# Amiga_USB_Serial_Adapter.net
KiCad netlist of a schematic drawn in EAGLE
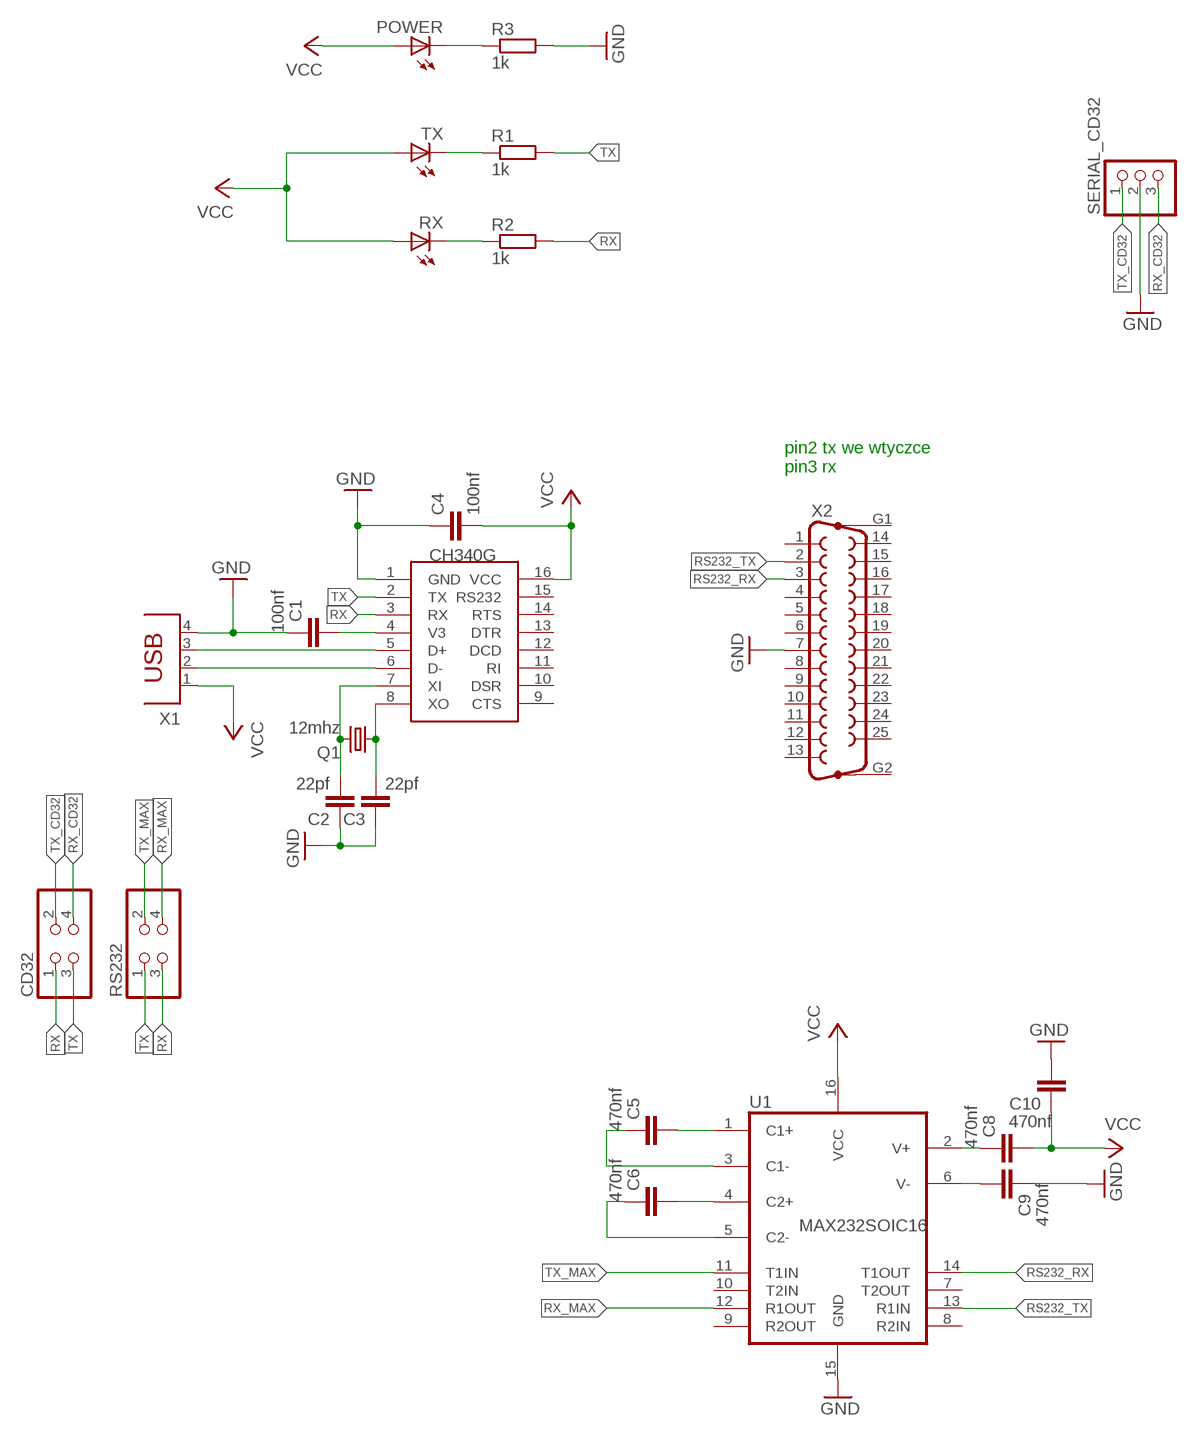
[diagram p0: schematic, sheet 1]

(export (version "E")
  (design (tool "Eeschema 10.0.6"))
  (components
    (comp (ref "C1")
      (value "100nf")
      (footprint "eagle-import:C0805")
      (libsource (lib "eagle-import") (part "C-EUC0805"))
    )
    (comp (ref "C2")
      (value "22pf")
      (footprint "eagle-import:C0805")
      (libsource (lib "eagle-import") (part "C-EUC0805"))
    )
    (comp (ref "C3")
      (value "22pf")
      (footprint "eagle-import:C0805")
      (libsource (lib "eagle-import") (part "C-EUC0805"))
    )
    (comp (ref "C4")
      (value "100nf")
      (footprint "eagle-import:C0805")
      (libsource (lib "eagle-import") (part "C-EUC0805"))
    )
    (comp (ref "C5")
      (value "470nf")
      (footprint "eagle-import:C0805")
      (libsource (lib "eagle-import") (part "C-EUC0805"))
    )
    (comp (ref "C6")
      (value "470nf")
      (footprint "eagle-import:C0805")
      (libsource (lib "eagle-import") (part "C-EUC0805"))
    )
    (comp (ref "C8")
      (value "470nf")
      (footprint "eagle-import:C0805")
      (libsource (lib "eagle-import") (part "C-EUC0805"))
    )
    (comp (ref "C9")
      (value "470nf")
      (footprint "eagle-import:C0805")
      (libsource (lib "eagle-import") (part "C-EUC0805"))
    )
    (comp (ref "C10")
      (value "470nf")
      (footprint "eagle-import:C0805")
      (libsource (lib "eagle-import") (part "C-EUC0805"))
    )
    (comp (ref "CD32")
      (value "PINHD-2X2")
      (footprint "eagle-import:2X02")
      (libsource (lib "eagle-import") (part "PINHD-2X2"))
    )
    (comp (ref "POWER")
      (value "LEDCHIPLED_0805")
      (footprint "eagle-import:CHIPLED_0805")
      (libsource (lib "eagle-import") (part "LEDCHIPLED_0805"))
    )
    (comp (ref "Q1")
      (value "12mhz")
      (footprint "eagle-import:HC49U-V")
      (libsource (lib "eagle-import") (part "CRYSTALHC49U-V"))
    )
    (comp (ref "R1")
      (value "1k")
      (footprint "eagle-import:R0805")
      (libsource (lib "eagle-import") (part "R-EU_R0805"))
    )
    (comp (ref "R2")
      (value "1k")
      (footprint "eagle-import:R0805")
      (libsource (lib "eagle-import") (part "R-EU_R0805"))
    )
    (comp (ref "R3")
      (value "1k")
      (footprint "eagle-import:R0805")
      (libsource (lib "eagle-import") (part "R-EU_R0805"))
    )
    (comp (ref "RS232")
      (value "PINHD-2X2")
      (footprint "eagle-import:2X02")
      (libsource (lib "eagle-import") (part "PINHD-2X2"))
    )
    (comp (ref "RX")
      (value "LEDCHIPLED_0805")
      (footprint "eagle-import:CHIPLED_0805")
      (libsource (lib "eagle-import") (part "LEDCHIPLED_0805"))
    )
    (comp (ref "SERIAL_CD32")
      (value "PINHD-1X3")
      (footprint "eagle-import:1X03")
      (libsource (lib "eagle-import") (part "PINHD-1X3"))
    )
    (comp (ref "TX")
      (value "LEDCHIPLED_0805")
      (footprint "eagle-import:CHIPLED_0805")
      (libsource (lib "eagle-import") (part "LEDCHIPLED_0805"))
    )
    (comp (ref "U$1")
      (value "CH340G")
      (footprint "eagle-import:SOIC16")
      (libsource (lib "eagle-import") (part "CH340G"))
    )
    (comp (ref "U1")
      (value "MAX232SOIC16")
      (footprint "eagle-import:SO016")
      (libsource (lib "eagle-import") (part "MAX232SOIC16"))
    )
    (comp (ref "X1")
      (value "PN61729")
      (footprint "eagle-import:PN61729")
      (libsource (lib "eagle-import") (part "PN61729"))
    )
    (comp (ref "X2")
      (value "F25HP")
      (footprint "eagle-import:F25HP")
      (libsource (lib "eagle-import") (part "F25HP"))
    )
  )
  (nets
    (net (code "1") (name "GND") (class "Default")
      (node (ref "C1") (pin "1") (pinfunction "1_1") (pintype "passive"))
      (node (ref "C10") (pin "2") (pinfunction "2_2") (pintype "passive"))
      (node (ref "C2") (pin "1") (pinfunction "1_1") (pintype "passive"))
      (node (ref "C3") (pin "1") (pinfunction "1_1") (pintype "passive"))
      (node (ref "C4") (pin "1") (pinfunction "1_1") (pintype "passive"))
      (node (ref "C9") (pin "1") (pinfunction "1_1") (pintype "passive"))
      (node (ref "R3") (pin "2") (pinfunction "2_2") (pintype "passive"))
      (node (ref "SERIAL_CD32") (pin "2") (pinfunction "2_2") (pintype "passive"))
      (node (ref "U$1") (pin "1") (pinfunction "GND_1") (pintype "bidirectional"))
      (node (ref "U1") (pin "15") (pinfunction "GND_15") (pintype "bidirectional"))
      (node (ref "X1") (pin "4") (pinfunction "4_4") (pintype "passive"))
      (node (ref "X2") (pin "7") (pinfunction "7_7") (pintype "passive"))
    )
    (net (code "2") (name "Net-(POWER-PadC)") (class "Default")
      (node (ref "POWER") (pin "C") (pinfunction "C_C") (pintype "passive"))
      (node (ref "R3") (pin "1") (pinfunction "1_1") (pintype "passive"))
    )
    (net (code "3") (name "Net-(R1-Pad1)") (class "Default")
      (node (ref "R1") (pin "1") (pinfunction "1_1") (pintype "passive"))
      (node (ref "TX") (pin "C") (pinfunction "C_C") (pintype "passive"))
    )
    (net (code "4") (name "Net-(R2-Pad1)") (class "Default")
      (node (ref "R2") (pin "1") (pinfunction "1_1") (pintype "passive"))
      (node (ref "RX") (pin "C") (pinfunction "C_C") (pintype "passive"))
    )
    (net (code "5") (name "Net-(U$1-D+)") (class "Default")
      (node (ref "U$1") (pin "5") (pinfunction "D+_5") (pintype "bidirectional"))
      (node (ref "X1") (pin "3") (pinfunction "3_3") (pintype "passive"))
    )
    (net (code "6") (name "Net-(U$1-D-)") (class "Default")
      (node (ref "U$1") (pin "6") (pinfunction "D-_6") (pintype "bidirectional"))
      (node (ref "X1") (pin "2") (pinfunction "2_2") (pintype "passive"))
    )
    (net (code "7") (name "Net-(U$1-V3)") (class "Default")
      (node (ref "C1") (pin "2") (pinfunction "2_2") (pintype "passive"))
      (node (ref "U$1") (pin "4") (pinfunction "V3_4") (pintype "bidirectional"))
    )
    (net (code "8") (name "Net-(U$1-XI)") (class "Default")
      (node (ref "C2") (pin "2") (pinfunction "2_2") (pintype "passive"))
      (node (ref "Q1") (pin "2") (pinfunction "2_2") (pintype "passive"))
      (node (ref "U$1") (pin "7") (pinfunction "XI_7") (pintype "bidirectional"))
    )
    (net (code "9") (name "Net-(U$1-XO)") (class "Default")
      (node (ref "C3") (pin "2") (pinfunction "2_2") (pintype "passive"))
      (node (ref "Q1") (pin "1") (pinfunction "1_1") (pintype "passive"))
      (node (ref "U$1") (pin "8") (pinfunction "XO_8") (pintype "bidirectional"))
    )
    (net (code "10") (name "Net-(U1-C1+)") (class "Default")
      (node (ref "C5") (pin "2") (pinfunction "2_2") (pintype "passive"))
      (node (ref "U1") (pin "1") (pinfunction "C1+_1") (pintype "bidirectional"))
    )
    (net (code "11") (name "Net-(U1-C1-)") (class "Default")
      (node (ref "C5") (pin "1") (pinfunction "1_1") (pintype "passive"))
      (node (ref "U1") (pin "3") (pinfunction "C1-_3") (pintype "bidirectional"))
    )
    (net (code "12") (name "Net-(U1-C2+)") (class "Default")
      (node (ref "C6") (pin "2") (pinfunction "2_2") (pintype "passive"))
      (node (ref "U1") (pin "4") (pinfunction "C2+_4") (pintype "bidirectional"))
    )
    (net (code "13") (name "Net-(U1-C2-)") (class "Default")
      (node (ref "C6") (pin "1") (pinfunction "1_1") (pintype "passive"))
      (node (ref "U1") (pin "5") (pinfunction "C2-_5") (pintype "bidirectional"))
    )
    (net (code "14") (name "Net-(U1-V+)") (class "Default")
      (node (ref "C8") (pin "1") (pinfunction "1_1") (pintype "passive"))
      (node (ref "U1") (pin "2") (pinfunction "V+_2") (pintype "bidirectional"))
    )
    (net (code "15") (name "Net-(U1-V-)") (class "Default")
      (node (ref "C9") (pin "2") (pinfunction "2_2") (pintype "passive"))
      (node (ref "U1") (pin "6") (pinfunction "V-_6") (pintype "bidirectional"))
    )
    (net (code "16") (name "RS232_RX") (class "Default")
      (node (ref "U1") (pin "14") (pinfunction "T1OUT_14") (pintype "output"))
      (node (ref "X2") (pin "3") (pinfunction "3_3") (pintype "passive"))
    )
    (net (code "17") (name "RS232_TX") (class "Default")
      (node (ref "U1") (pin "13") (pinfunction "R1IN_13") (pintype "input"))
      (node (ref "X2") (pin "2") (pinfunction "2_2") (pintype "passive"))
    )
    (net (code "18") (name "RX") (class "Default")
      (node (ref "CD32") (pin "1") (pinfunction "1_1") (pintype "passive"))
      (node (ref "R2") (pin "2") (pinfunction "2_2") (pintype "passive"))
      (node (ref "RS232") (pin "3") (pinfunction "3_3") (pintype "passive"))
      (node (ref "U$1") (pin "3") (pinfunction "RX_3") (pintype "bidirectional"))
    )
    (net (code "19") (name "RX_CD32") (class "Default")
      (node (ref "CD32") (pin "4") (pinfunction "4_4") (pintype "passive"))
      (node (ref "SERIAL_CD32") (pin "3") (pinfunction "3_3") (pintype "passive"))
    )
    (net (code "20") (name "RX_MAX") (class "Default")
      (node (ref "RS232") (pin "4") (pinfunction "4_4") (pintype "passive"))
      (node (ref "U1") (pin "12") (pinfunction "R1OUT_12") (pintype "output"))
    )
    (net (code "21") (name "TX") (class "Default")
      (node (ref "CD32") (pin "3") (pinfunction "3_3") (pintype "passive"))
      (node (ref "R1") (pin "2") (pinfunction "2_2") (pintype "passive"))
      (node (ref "RS232") (pin "1") (pinfunction "1_1") (pintype "passive"))
      (node (ref "U$1") (pin "2") (pinfunction "TX_2") (pintype "bidirectional"))
    )
    (net (code "22") (name "TX_CD32") (class "Default")
      (node (ref "CD32") (pin "2") (pinfunction "2_2") (pintype "passive"))
      (node (ref "SERIAL_CD32") (pin "1") (pinfunction "1_1") (pintype "passive"))
    )
    (net (code "23") (name "TX_MAX") (class "Default")
      (node (ref "RS232") (pin "2") (pinfunction "2_2") (pintype "passive"))
      (node (ref "U1") (pin "11") (pinfunction "T1IN_11") (pintype "input"))
    )
    (net (code "24") (name "VCC") (class "Default")
      (node (ref "C10") (pin "1") (pinfunction "1_1") (pintype "passive"))
      (node (ref "C4") (pin "2") (pinfunction "2_2") (pintype "passive"))
      (node (ref "C8") (pin "2") (pinfunction "2_2") (pintype "passive"))
      (node (ref "POWER") (pin "A") (pinfunction "A_A") (pintype "passive"))
      (node (ref "RX") (pin "A") (pinfunction "A_A") (pintype "passive"))
      (node (ref "TX") (pin "A") (pinfunction "A_A") (pintype "passive"))
      (node (ref "U$1") (pin "16") (pinfunction "VCC_16") (pintype "bidirectional"))
      (node (ref "U1") (pin "16") (pinfunction "VCC_16") (pintype "bidirectional"))
      (node (ref "X1") (pin "1") (pinfunction "1_1") (pintype "passive"))
    )
    (net (code "25") (name "unconnected-(U$1-CTS-Pad9)") (class "Default")
      (node (ref "U$1") (pin "9") (pinfunction "CTS_9") (pintype "bidirectional"))
    )
    (net (code "26") (name "unconnected-(U$1-DCD-Pad12)") (class "Default")
      (node (ref "U$1") (pin "12") (pinfunction "DCD_12") (pintype "bidirectional"))
    )
    (net (code "27") (name "unconnected-(U$1-DSR-Pad10)") (class "Default")
      (node (ref "U$1") (pin "10") (pinfunction "DSR_10") (pintype "bidirectional"))
    )
    (net (code "28") (name "unconnected-(U$1-DTR-Pad13)") (class "Default")
      (node (ref "U$1") (pin "13") (pinfunction "DTR_13") (pintype "bidirectional"))
    )
    (net (code "29") (name "unconnected-(U$1-RI-Pad11)") (class "Default")
      (node (ref "U$1") (pin "11") (pinfunction "RI_11") (pintype "bidirectional"))
    )
    (net (code "30") (name "unconnected-(U$1-RS232-Pad15)") (class "Default")
      (node (ref "U$1") (pin "15") (pinfunction "RS232_15") (pintype "bidirectional"))
    )
    (net (code "31") (name "unconnected-(U$1-RTS-Pad14)") (class "Default")
      (node (ref "U$1") (pin "14") (pinfunction "RTS_14") (pintype "bidirectional"))
    )
    (net (code "32") (name "unconnected-(U1-R2IN-Pad8)") (class "Default")
      (node (ref "U1") (pin "8") (pinfunction "R2IN_8") (pintype "input"))
    )
    (net (code "33") (name "unconnected-(U1-R2OUT-Pad9)") (class "Default")
      (node (ref "U1") (pin "9") (pinfunction "R2OUT_9") (pintype "output"))
    )
    (net (code "34") (name "unconnected-(U1-T2IN-Pad10)") (class "Default")
      (node (ref "U1") (pin "10") (pinfunction "T2IN_10") (pintype "input"))
    )
    (net (code "35") (name "unconnected-(U1-T2OUT-Pad7)") (class "Default")
      (node (ref "U1") (pin "7") (pinfunction "T2OUT_7") (pintype "output"))
    )
    (net (code "36") (name "unconnected-(X2-Pad1)") (class "Default")
      (node (ref "X2") (pin "1") (pinfunction "1_1") (pintype "passive"))
    )
    (net (code "37") (name "unconnected-(X2-Pad4)") (class "Default")
      (node (ref "X2") (pin "4") (pinfunction "4_4") (pintype "passive"))
    )
    (net (code "38") (name "unconnected-(X2-Pad5)") (class "Default")
      (node (ref "X2") (pin "5") (pinfunction "5_5") (pintype "passive"))
    )
    (net (code "39") (name "unconnected-(X2-Pad6)") (class "Default")
      (node (ref "X2") (pin "6") (pinfunction "6_6") (pintype "passive"))
    )
    (net (code "40") (name "unconnected-(X2-Pad8)") (class "Default")
      (node (ref "X2") (pin "8") (pinfunction "8_8") (pintype "passive"))
    )
    (net (code "41") (name "unconnected-(X2-Pad9)") (class "Default")
      (node (ref "X2") (pin "9") (pinfunction "9_9") (pintype "passive"))
    )
    (net (code "42") (name "unconnected-(X2-Pad10)") (class "Default")
      (node (ref "X2") (pin "10") (pinfunction "10_10") (pintype "passive"))
    )
    (net (code "43") (name "unconnected-(X2-Pad11)") (class "Default")
      (node (ref "X2") (pin "11") (pinfunction "11_11") (pintype "passive"))
    )
    (net (code "44") (name "unconnected-(X2-Pad12)") (class "Default")
      (node (ref "X2") (pin "12") (pinfunction "12_12") (pintype "passive"))
    )
    (net (code "45") (name "unconnected-(X2-Pad13)") (class "Default")
      (node (ref "X2") (pin "13") (pinfunction "13_13") (pintype "passive"))
    )
    (net (code "46") (name "unconnected-(X2-Pad14)") (class "Default")
      (node (ref "X2") (pin "14") (pinfunction "14_14") (pintype "passive"))
    )
    (net (code "47") (name "unconnected-(X2-Pad15)") (class "Default")
      (node (ref "X2") (pin "15") (pinfunction "15_15") (pintype "passive"))
    )
    (net (code "48") (name "unconnected-(X2-Pad16)") (class "Default")
      (node (ref "X2") (pin "16") (pinfunction "16_16") (pintype "passive"))
    )
    (net (code "49") (name "unconnected-(X2-Pad17)") (class "Default")
      (node (ref "X2") (pin "17") (pinfunction "17_17") (pintype "passive"))
    )
    (net (code "50") (name "unconnected-(X2-Pad18)") (class "Default")
      (node (ref "X2") (pin "18") (pinfunction "18_18") (pintype "passive"))
    )
    (net (code "51") (name "unconnected-(X2-Pad19)") (class "Default")
      (node (ref "X2") (pin "19") (pinfunction "19_19") (pintype "passive"))
    )
    (net (code "52") (name "unconnected-(X2-Pad20)") (class "Default")
      (node (ref "X2") (pin "20") (pinfunction "20_20") (pintype "passive"))
    )
    (net (code "53") (name "unconnected-(X2-Pad21)") (class "Default")
      (node (ref "X2") (pin "21") (pinfunction "21_21") (pintype "passive"))
    )
    (net (code "54") (name "unconnected-(X2-Pad22)") (class "Default")
      (node (ref "X2") (pin "22") (pinfunction "22_22") (pintype "passive"))
    )
    (net (code "55") (name "unconnected-(X2-Pad23)") (class "Default")
      (node (ref "X2") (pin "23") (pinfunction "23_23") (pintype "passive"))
    )
    (net (code "56") (name "unconnected-(X2-Pad24)") (class "Default")
      (node (ref "X2") (pin "24") (pinfunction "24_24") (pintype "passive"))
    )
    (net (code "57") (name "unconnected-(X2-Pad25)") (class "Default")
      (node (ref "X2") (pin "25") (pinfunction "25_25") (pintype "passive"))
    )
    (net (code "58") (name "unconnected-(X2-PadG1)") (class "Default")
      (node (ref "X2") (pin "G1") (pinfunction "G1_G1") (pintype "passive"))
    )
    (net (code "59") (name "unconnected-(X2-PadG2)") (class "Default")
      (node (ref "X2") (pin "G2") (pinfunction "G2_G2") (pintype "passive"))
    )
  )
)
